# ECG.net
KiCad netlist of a schematic drawn in EAGLE
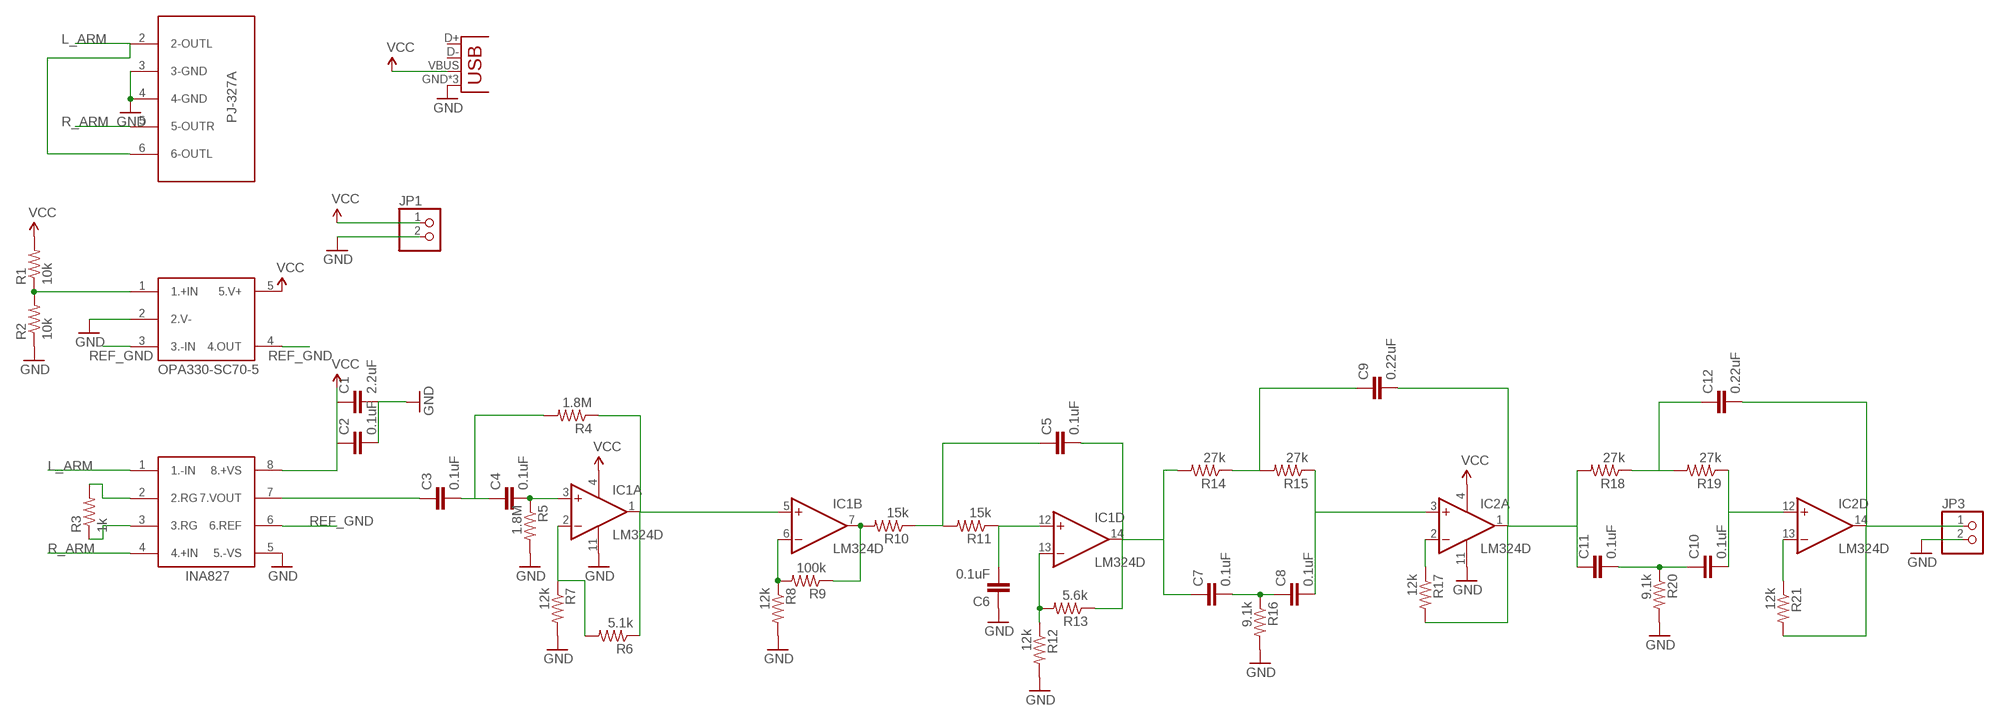
[diagram p0: schematic, sheet 1]

(export (version "E")
  (design (tool "Eeschema 10.0.6"))
  (components
    (comp (ref "C1")
      (value "2.2uF")
      (footprint "eagle-import:CAP-PTH-LARGE")
      (libsource (lib "eagle-import") (part "CAPPTH3"))
    )
    (comp (ref "C2")
      (value "0.1uF")
      (footprint "eagle-import:CAP-PTH-LARGE")
      (libsource (lib "eagle-import") (part "CAPPTH3"))
    )
    (comp (ref "C3")
      (value "0.1uF")
      (footprint "eagle-import:CAP-PTH-LARGE")
      (libsource (lib "eagle-import") (part "CAPPTH3"))
    )
    (comp (ref "C4")
      (value "0.1uF")
      (footprint "eagle-import:CAP-PTH-LARGE")
      (libsource (lib "eagle-import") (part "CAPPTH3"))
    )
    (comp (ref "C5")
      (value "0.1uF")
      (footprint "eagle-import:CAP-PTH-LARGE")
      (libsource (lib "eagle-import") (part "CAPPTH3"))
    )
    (comp (ref "C6")
      (value "0.1uF")
      (footprint "eagle-import:CAP-PTH-LARGE")
      (libsource (lib "eagle-import") (part "CAPPTH3"))
    )
    (comp (ref "C7")
      (value "0.1uF")
      (footprint "eagle-import:CAP-PTH-LARGE")
      (libsource (lib "eagle-import") (part "CAPPTH3"))
    )
    (comp (ref "C8")
      (value "0.1uF")
      (footprint "eagle-import:CAP-PTH-LARGE")
      (libsource (lib "eagle-import") (part "CAPPTH3"))
    )
    (comp (ref "C9")
      (value "0.22uF")
      (footprint "eagle-import:CAP-PTH-LARGE")
      (libsource (lib "eagle-import") (part "CAPPTH3"))
    )
    (comp (ref "C10")
      (value "0.1uF")
      (footprint "eagle-import:CAP-PTH-LARGE")
      (libsource (lib "eagle-import") (part "CAPPTH3"))
    )
    (comp (ref "C11")
      (value "0.1uF")
      (footprint "eagle-import:CAP-PTH-LARGE")
      (libsource (lib "eagle-import") (part "CAPPTH3"))
    )
    (comp (ref "C12")
      (value "0.22uF")
      (footprint "eagle-import:CAP-PTH-LARGE")
      (libsource (lib "eagle-import") (part "CAPPTH3"))
    )
    (comp (ref "IC1")
      (value "LM324D")
      (footprint "eagle-import:SO14")
      (libsource (lib "eagle-import") (part "LM324D"))
    )
    (comp (ref "IC2")
      (value "LM324D")
      (footprint "eagle-import:SO14")
      (libsource (lib "eagle-import") (part "LM324D"))
    )
    (comp (ref "JP1")
      (value "PINHD-1X2")
      (footprint "eagle-import:1X02")
      (libsource (lib "eagle-import") (part "PINHD-1X2"))
    )
    (comp (ref "JP2")
      (value "USB-MICROB")
      (footprint "eagle-import:USB-MICROB")
      (libsource (lib "eagle-import") (part "USB-MICROB"))
    )
    (comp (ref "JP3")
      (value "PINHD-1X2")
      (footprint "eagle-import:1X02")
      (libsource (lib "eagle-import") (part "PINHD-1X2"))
    )
    (comp (ref "R1")
      (value "10k")
      (footprint "eagle-import:AXIAL-0.4")
      (libsource (lib "eagle-import") (part "RESISTORPTH-1/4W"))
    )
    (comp (ref "R2")
      (value "10k")
      (footprint "eagle-import:AXIAL-0.4")
      (libsource (lib "eagle-import") (part "RESISTORPTH-1/4W"))
    )
    (comp (ref "R3")
      (value "1k")
      (footprint "eagle-import:AXIAL-0.4")
      (libsource (lib "eagle-import") (part "RESISTORPTH-1/4W"))
    )
    (comp (ref "R4")
      (value "1.8M")
      (footprint "eagle-import:AXIAL-0.4")
      (libsource (lib "eagle-import") (part "RESISTORPTH-1/4W"))
    )
    (comp (ref "R5")
      (value "1.8M")
      (footprint "eagle-import:AXIAL-0.4")
      (libsource (lib "eagle-import") (part "RESISTORPTH-1/4W"))
    )
    (comp (ref "R6")
      (value "5.1k")
      (footprint "eagle-import:AXIAL-0.4")
      (libsource (lib "eagle-import") (part "RESISTORPTH-1/4W"))
    )
    (comp (ref "R7")
      (value "12k")
      (footprint "eagle-import:AXIAL-0.4")
      (libsource (lib "eagle-import") (part "RESISTORPTH-1/4W"))
    )
    (comp (ref "R8")
      (value "12k")
      (footprint "eagle-import:AXIAL-0.4")
      (libsource (lib "eagle-import") (part "RESISTORPTH-1/4W"))
    )
    (comp (ref "R9")
      (value "100k")
      (footprint "eagle-import:AXIAL-0.4")
      (libsource (lib "eagle-import") (part "RESISTORPTH-1/4W"))
    )
    (comp (ref "R10")
      (value "15k")
      (footprint "eagle-import:AXIAL-0.4")
      (libsource (lib "eagle-import") (part "RESISTORPTH-1/4W"))
    )
    (comp (ref "R11")
      (value "15k")
      (footprint "eagle-import:AXIAL-0.4")
      (libsource (lib "eagle-import") (part "RESISTORPTH-1/4W"))
    )
    (comp (ref "R12")
      (value "12k")
      (footprint "eagle-import:AXIAL-0.4")
      (libsource (lib "eagle-import") (part "RESISTORPTH-1/4W"))
    )
    (comp (ref "R13")
      (value "5.6k")
      (footprint "eagle-import:AXIAL-0.4")
      (libsource (lib "eagle-import") (part "RESISTORPTH-1/4W"))
    )
    (comp (ref "R14")
      (value "27k")
      (footprint "eagle-import:AXIAL-0.4")
      (libsource (lib "eagle-import") (part "RESISTORPTH-1/4W"))
    )
    (comp (ref "R15")
      (value "27k")
      (footprint "eagle-import:AXIAL-0.4")
      (libsource (lib "eagle-import") (part "RESISTORPTH-1/4W"))
    )
    (comp (ref "R16")
      (value "9.1k")
      (footprint "eagle-import:AXIAL-0.4")
      (libsource (lib "eagle-import") (part "RESISTORPTH-1/4W"))
    )
    (comp (ref "R17")
      (value "12k")
      (footprint "eagle-import:AXIAL-0.4")
      (libsource (lib "eagle-import") (part "RESISTORPTH-1/4W"))
    )
    (comp (ref "R18")
      (value "27k")
      (footprint "eagle-import:AXIAL-0.4")
      (libsource (lib "eagle-import") (part "RESISTORPTH-1/4W"))
    )
    (comp (ref "R19")
      (value "27k")
      (footprint "eagle-import:AXIAL-0.4")
      (libsource (lib "eagle-import") (part "RESISTORPTH-1/4W"))
    )
    (comp (ref "R20")
      (value "9.1k")
      (footprint "eagle-import:AXIAL-0.4")
      (libsource (lib "eagle-import") (part "RESISTORPTH-1/4W"))
    )
    (comp (ref "R21")
      (value "12k")
      (footprint "eagle-import:AXIAL-0.4")
      (libsource (lib "eagle-import") (part "RESISTORPTH-1/4W"))
    )
    (comp (ref "U$1")
      (value "OPA330-SC70-5")
      (footprint "eagle-import:OPA330-SC70-5")
      (libsource (lib "eagle-import") (part "OPA330-SC70-5"))
    )
    (comp (ref "U$2")
      (value "INA827")
      (footprint "eagle-import:INA827")
      (libsource (lib "eagle-import") (part "INA827"))
    )
    (comp (ref "U$3")
      (value "PJ-327A")
      (footprint "eagle-import:PJ-327A")
      (libsource (lib "eagle-import") (part "PJ-327A"))
    )
  )
  (nets
    (net (code "1") (name "/L_ARM") (class "Default")
      (node (ref "U$2") (pin "1") (pinfunction "1.-IN_1") (pintype "bidirectional"))
      (node (ref "U$3") (pin "2") (pinfunction "2-OUTL_2") (pintype "bidirectional"))
      (node (ref "U$3") (pin "6") (pinfunction "6-OUTL_6") (pintype "bidirectional"))
    )
    (net (code "2") (name "/REF_GND") (class "Default")
      (node (ref "U$1") (pin "3") (pinfunction "3.-IN_3") (pintype "bidirectional"))
      (node (ref "U$1") (pin "4") (pinfunction "4.OUT_4") (pintype "bidirectional"))
      (node (ref "U$2") (pin "6") (pinfunction "6.REF_6") (pintype "bidirectional"))
    )
    (net (code "3") (name "/R_ARM") (class "Default")
      (node (ref "U$2") (pin "4") (pinfunction "4.+IN_4") (pintype "bidirectional"))
      (node (ref "U$3") (pin "5") (pinfunction "5-OUTR_5") (pintype "bidirectional"))
    )
    (net (code "4") (name "GND") (class "Default")
      (node (ref "C1") (pin "2") (pinfunction "2_2") (pintype "passive"))
      (node (ref "C2") (pin "2") (pinfunction "2_2") (pintype "passive"))
      (node (ref "C6") (pin "1") (pinfunction "1_1") (pintype "passive"))
      (node (ref "IC1") (pin "11") (pinfunction "V-_11") (pintype "power_in"))
      (node (ref "IC2") (pin "11") (pinfunction "V-_11") (pintype "power_in"))
      (node (ref "JP1") (pin "2") (pinfunction "2_2") (pintype "passive"))
      (node (ref "JP2") (pin "GND") (pinfunction "GND_GND") (pintype "bidirectional"))
      (node (ref "JP2") (pin "MT1") (pinfunction "GND_MT1") (pintype "bidirectional"))
      (node (ref "JP2") (pin "MT2") (pinfunction "GND_MT2") (pintype "bidirectional"))
      (node (ref "JP3") (pin "2") (pinfunction "2_2") (pintype "passive"))
      (node (ref "R12") (pin "P$2") (pinfunction "2_P$2") (pintype "passive"))
      (node (ref "R16") (pin "P$2") (pinfunction "2_P$2") (pintype "passive"))
      (node (ref "R2") (pin "P$1") (pinfunction "1_P$1") (pintype "passive"))
      (node (ref "R20") (pin "P$2") (pinfunction "2_P$2") (pintype "passive"))
      (node (ref "R5") (pin "P$2") (pinfunction "2_P$2") (pintype "passive"))
      (node (ref "R7") (pin "P$2") (pinfunction "2_P$2") (pintype "passive"))
      (node (ref "R8") (pin "P$2") (pinfunction "2_P$2") (pintype "passive"))
      (node (ref "U$1") (pin "2") (pinfunction "2.V-_2") (pintype "bidirectional"))
      (node (ref "U$2") (pin "5") (pinfunction "5.-VS_5") (pintype "bidirectional"))
      (node (ref "U$3") (pin "3") (pinfunction "3-GND_3") (pintype "bidirectional"))
      (node (ref "U$3") (pin "4") (pinfunction "4-GND_4") (pintype "bidirectional"))
    )
    (net (code "5") (name "Net-(IC1A-+IN)") (class "Default")
      (node (ref "C4") (pin "2") (pinfunction "2_2") (pintype "passive"))
      (node (ref "IC1") (pin "3") (pinfunction "+IN_3") (pintype "input"))
      (node (ref "R5") (pin "P$1") (pinfunction "1_P$1") (pintype "passive"))
    )
    (net (code "6") (name "Net-(IC1A--IN)") (class "Default")
      (node (ref "IC1") (pin "2") (pinfunction "-IN_2") (pintype "input"))
      (node (ref "R6") (pin "P$2") (pinfunction "2_P$2") (pintype "passive"))
      (node (ref "R7") (pin "P$1") (pinfunction "1_P$1") (pintype "passive"))
    )
    (net (code "7") (name "Net-(IC1A-OUT)") (class "Default")
      (node (ref "IC1") (pin "1") (pinfunction "OUT_1") (pintype "output"))
      (node (ref "IC1") (pin "5") (pinfunction "+IN_5") (pintype "input"))
      (node (ref "R4") (pin "P$1") (pinfunction "1_P$1") (pintype "passive"))
      (node (ref "R6") (pin "P$1") (pinfunction "1_P$1") (pintype "passive"))
    )
    (net (code "8") (name "Net-(IC1B--IN)") (class "Default")
      (node (ref "IC1") (pin "6") (pinfunction "-IN_6") (pintype "input"))
      (node (ref "R8") (pin "P$1") (pinfunction "1_P$1") (pintype "passive"))
      (node (ref "R9") (pin "P$2") (pinfunction "2_P$2") (pintype "passive"))
    )
    (net (code "9") (name "Net-(IC1B-OUT)") (class "Default")
      (node (ref "IC1") (pin "7") (pinfunction "OUT_7") (pintype "output"))
      (node (ref "R10") (pin "P$2") (pinfunction "2_P$2") (pintype "passive"))
      (node (ref "R9") (pin "P$1") (pinfunction "1_P$1") (pintype "passive"))
    )
    (net (code "10") (name "Net-(IC1D-+IN)") (class "Default")
      (node (ref "C6") (pin "2") (pinfunction "2_2") (pintype "passive"))
      (node (ref "IC1") (pin "12") (pinfunction "+IN_12") (pintype "input"))
      (node (ref "R11") (pin "P$1") (pinfunction "1_P$1") (pintype "passive"))
    )
    (net (code "11") (name "Net-(IC1D--IN)") (class "Default")
      (node (ref "IC1") (pin "13") (pinfunction "-IN_13") (pintype "input"))
      (node (ref "R12") (pin "P$1") (pinfunction "1_P$1") (pintype "passive"))
      (node (ref "R13") (pin "P$2") (pinfunction "2_P$2") (pintype "passive"))
    )
    (net (code "12") (name "Net-(IC1D-OUT)") (class "Default")
      (node (ref "C5") (pin "2") (pinfunction "2_2") (pintype "passive"))
      (node (ref "C7") (pin "1") (pinfunction "1_1") (pintype "passive"))
      (node (ref "IC1") (pin "14") (pinfunction "OUT_14") (pintype "output"))
      (node (ref "R13") (pin "P$1") (pinfunction "1_P$1") (pintype "passive"))
      (node (ref "R14") (pin "P$2") (pinfunction "2_P$2") (pintype "passive"))
    )
    (net (code "13") (name "Net-(IC2A-+IN)") (class "Default")
      (node (ref "C8") (pin "2") (pinfunction "2_2") (pintype "passive"))
      (node (ref "IC2") (pin "3") (pinfunction "+IN_3") (pintype "input"))
      (node (ref "R15") (pin "P$1") (pinfunction "1_P$1") (pintype "passive"))
    )
    (net (code "14") (name "Net-(IC2A--IN)") (class "Default")
      (node (ref "IC2") (pin "2") (pinfunction "-IN_2") (pintype "input"))
      (node (ref "R17") (pin "P$1") (pinfunction "1_P$1") (pintype "passive"))
    )
    (net (code "15") (name "Net-(IC2A-OUT)") (class "Default")
      (node (ref "C11") (pin "1") (pinfunction "1_1") (pintype "passive"))
      (node (ref "C9") (pin "2") (pinfunction "2_2") (pintype "passive"))
      (node (ref "IC2") (pin "1") (pinfunction "OUT_1") (pintype "output"))
      (node (ref "R17") (pin "P$2") (pinfunction "2_P$2") (pintype "passive"))
      (node (ref "R18") (pin "P$2") (pinfunction "2_P$2") (pintype "passive"))
    )
    (net (code "16") (name "Net-(IC2D-+IN)") (class "Default")
      (node (ref "C10") (pin "2") (pinfunction "2_2") (pintype "passive"))
      (node (ref "IC2") (pin "12") (pinfunction "+IN_12") (pintype "input"))
      (node (ref "R19") (pin "P$1") (pinfunction "1_P$1") (pintype "passive"))
    )
    (net (code "17") (name "Net-(IC2D--IN)") (class "Default")
      (node (ref "IC2") (pin "13") (pinfunction "-IN_13") (pintype "input"))
      (node (ref "R21") (pin "P$1") (pinfunction "1_P$1") (pintype "passive"))
    )
    (net (code "18") (name "Net-(IC2D-OUT)") (class "Default")
      (node (ref "C12") (pin "2") (pinfunction "2_2") (pintype "passive"))
      (node (ref "IC2") (pin "14") (pinfunction "OUT_14") (pintype "output"))
      (node (ref "JP3") (pin "1") (pinfunction "1_1") (pintype "passive"))
      (node (ref "R21") (pin "P$2") (pinfunction "2_P$2") (pintype "passive"))
    )
    (net (code "19") (name "Net-(R1-1)") (class "Default")
      (node (ref "R1") (pin "P$1") (pinfunction "1_P$1") (pintype "passive"))
      (node (ref "R2") (pin "P$2") (pinfunction "2_P$2") (pintype "passive"))
      (node (ref "U$1") (pin "1") (pinfunction "1.+IN_1") (pintype "bidirectional"))
    )
    (net (code "20") (name "Net-(R3-1)") (class "Default")
      (node (ref "R3") (pin "P$1") (pinfunction "1_P$1") (pintype "passive"))
      (node (ref "U$2") (pin "3") (pinfunction "3.RG_3") (pintype "bidirectional"))
    )
    (net (code "21") (name "Net-(R3-2)") (class "Default")
      (node (ref "R3") (pin "P$2") (pinfunction "2_P$2") (pintype "passive"))
      (node (ref "U$2") (pin "2") (pinfunction "2.RG_2") (pintype "bidirectional"))
    )
    (net (code "22") (name "Net-(R4-2)") (class "Default")
      (node (ref "C3") (pin "2") (pinfunction "2_2") (pintype "passive"))
      (node (ref "C4") (pin "1") (pinfunction "1_1") (pintype "passive"))
      (node (ref "R4") (pin "P$2") (pinfunction "2_P$2") (pintype "passive"))
    )
    (net (code "23") (name "Net-(R10-1)") (class "Default")
      (node (ref "C5") (pin "1") (pinfunction "1_1") (pintype "passive"))
      (node (ref "R10") (pin "P$1") (pinfunction "1_P$1") (pintype "passive"))
      (node (ref "R11") (pin "P$2") (pinfunction "2_P$2") (pintype "passive"))
    )
    (net (code "24") (name "Net-(R14-1)") (class "Default")
      (node (ref "C9") (pin "1") (pinfunction "1_1") (pintype "passive"))
      (node (ref "R14") (pin "P$1") (pinfunction "1_P$1") (pintype "passive"))
      (node (ref "R15") (pin "P$2") (pinfunction "2_P$2") (pintype "passive"))
    )
    (net (code "25") (name "Net-(R16-1)") (class "Default")
      (node (ref "C7") (pin "2") (pinfunction "2_2") (pintype "passive"))
      (node (ref "C8") (pin "1") (pinfunction "1_1") (pintype "passive"))
      (node (ref "R16") (pin "P$1") (pinfunction "1_P$1") (pintype "passive"))
    )
    (net (code "26") (name "Net-(R18-1)") (class "Default")
      (node (ref "C12") (pin "1") (pinfunction "1_1") (pintype "passive"))
      (node (ref "R18") (pin "P$1") (pinfunction "1_P$1") (pintype "passive"))
      (node (ref "R19") (pin "P$2") (pinfunction "2_P$2") (pintype "passive"))
    )
    (net (code "27") (name "Net-(R20-1)") (class "Default")
      (node (ref "C10") (pin "1") (pinfunction "1_1") (pintype "passive"))
      (node (ref "C11") (pin "2") (pinfunction "2_2") (pintype "passive"))
      (node (ref "R20") (pin "P$1") (pinfunction "1_P$1") (pintype "passive"))
    )
    (net (code "28") (name "Net-(U$2-7.VOUT)") (class "Default")
      (node (ref "C3") (pin "1") (pinfunction "1_1") (pintype "passive"))
      (node (ref "U$2") (pin "7") (pinfunction "7.VOUT_7") (pintype "bidirectional"))
    )
    (net (code "29") (name "VCC") (class "Default")
      (node (ref "C1") (pin "1") (pinfunction "1_1") (pintype "passive"))
      (node (ref "C2") (pin "1") (pinfunction "1_1") (pintype "passive"))
      (node (ref "IC1") (pin "4") (pinfunction "V+_4") (pintype "power_in"))
      (node (ref "IC2") (pin "4") (pinfunction "V+_4") (pintype "power_in"))
      (node (ref "JP1") (pin "1") (pinfunction "1_1") (pintype "passive"))
      (node (ref "JP2") (pin "VBUS") (pinfunction "VBUS_VBUS") (pintype "bidirectional"))
      (node (ref "R1") (pin "P$2") (pinfunction "2_P$2") (pintype "passive"))
      (node (ref "U$1") (pin "5") (pinfunction "5.V+_5") (pintype "bidirectional"))
      (node (ref "U$2") (pin "8") (pinfunction "8.+VS_8") (pintype "bidirectional"))
    )
    (net (code "30") (name "unconnected-(JP2-PadD+)") (class "Default")
      (node (ref "JP2") (pin "D+") (pinfunction "D+_D+") (pintype "bidirectional"))
    )
    (net (code "31") (name "unconnected-(JP2-PadD-)") (class "Default")
      (node (ref "JP2") (pin "D-") (pinfunction "D-_D-") (pintype "bidirectional"))
    )
  )
)
